# BaseSMD.net
KiCad netlist of a schematic drawn in EAGLE
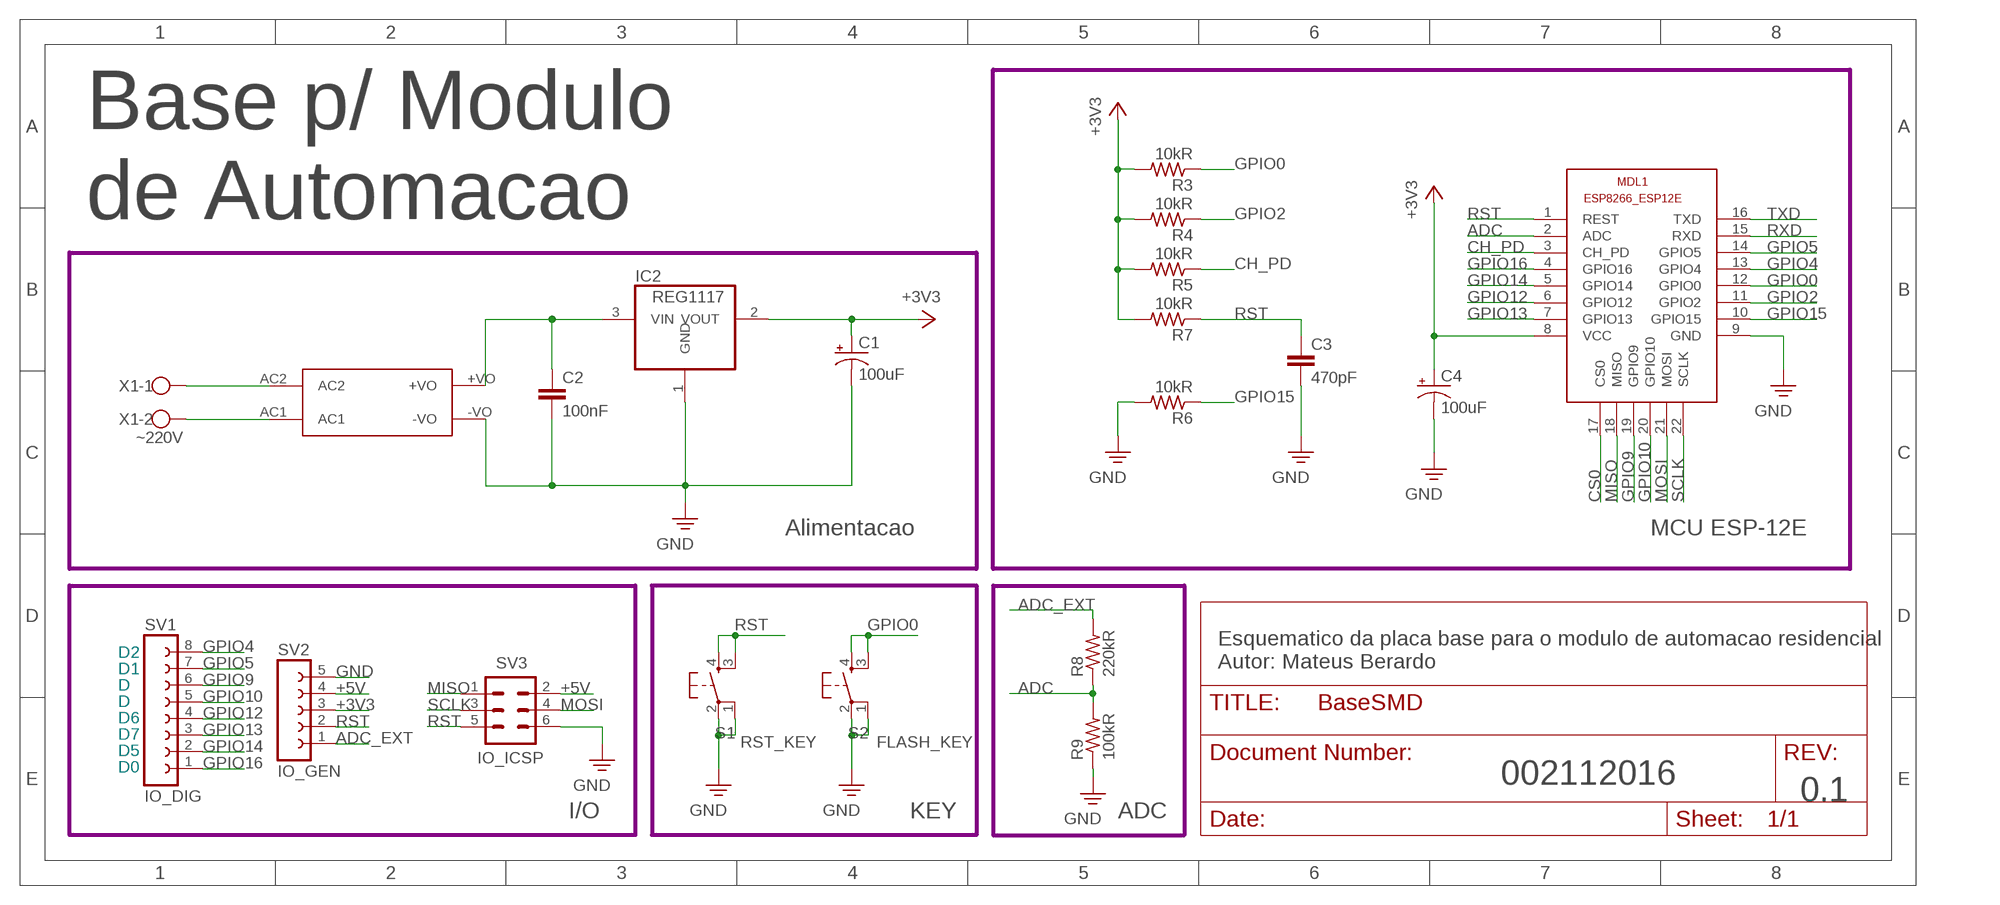
[diagram p0: schematic, sheet 1]

(export (version "E")
  (design (tool "Eeschema 10.0.6"))
  (components
    (comp (ref "C1")
      (value "100uF")
      (footprint "eagle-import:153CLV-0810")
      (libsource (lib "eagle-import") (part "CPOL-US153CLV-0810"))
    )
    (comp (ref "C2")
      (value "100nF")
      (footprint "eagle-import:C1206")
      (libsource (lib "eagle-import") (part "C-EUC1206"))
    )
    (comp (ref "C3")
      (value "470pF")
      (footprint "eagle-import:C1206")
      (libsource (lib "eagle-import") (part "C-EUC1206"))
    )
    (comp (ref "C4")
      (value "100uF")
      (footprint "eagle-import:153CLV-0810")
      (libsource (lib "eagle-import") (part "CPOL-US153CLV-0810"))
    )
    (comp (ref "IC2")
      (value "REG1117")
      (footprint "eagle-import:SOT223")
      (libsource (lib "eagle-import") (part "REG1117"))
    )
    (comp (ref "MDL1")
      (value "MCU ESP")
      (footprint "eagle-import:ESP8266-ESP12E")
      (libsource (lib "eagle-import") (part "ESP8266-12EESP8266-ESP12E"))
    )
    (comp (ref "R3")
      (value "10kR")
      (footprint "eagle-import:M1206")
      (libsource (lib "eagle-import") (part "R-US_M1206"))
    )
    (comp (ref "R4")
      (value "10kR")
      (footprint "eagle-import:M1206")
      (libsource (lib "eagle-import") (part "R-US_M1206"))
    )
    (comp (ref "R5")
      (value "10kR")
      (footprint "eagle-import:M1206")
      (libsource (lib "eagle-import") (part "R-US_M1206"))
    )
    (comp (ref "R6")
      (value "10kR")
      (footprint "eagle-import:M1206")
      (libsource (lib "eagle-import") (part "R-US_M1206"))
    )
    (comp (ref "R7")
      (value "10kR")
      (footprint "eagle-import:M1206")
      (libsource (lib "eagle-import") (part "R-US_M1206"))
    )
    (comp (ref "R8")
      (value "220kR")
      (footprint "eagle-import:R1206")
      (libsource (lib "eagle-import") (part "R-US_R1206"))
    )
    (comp (ref "R9")
      (value "100kR")
      (footprint "eagle-import:R1206")
      (libsource (lib "eagle-import") (part "R-US_R1206"))
    )
    (comp (ref "S1")
      (value "RST_KEY")
      (footprint "eagle-import:BT4X4")
      (libsource (lib "eagle-import") (part "10-XX4X4SMD"))
    )
    (comp (ref "S2")
      (value "FLASH_KEY")
      (footprint "eagle-import:BT4X4")
      (libsource (lib "eagle-import") (part "10-XX4X4SMD"))
    )
    (comp (ref "SV1")
      (value "IO_DIG")
      (footprint "eagle-import:FE08")
      (libsource (lib "eagle-import") (part "FE08-1"))
    )
    (comp (ref "SV2")
      (value "IO_GEN")
      (footprint "eagle-import:FE05-1")
      (libsource (lib "eagle-import") (part "FE05-1"))
    )
    (comp (ref "SV3")
      (value "IO_ICSP")
      (footprint "eagle-import:MA03-2")
      (libsource (lib "eagle-import") (part "MA03-2"))
    )
    (comp (ref "U$1")
      (value "HLK-PM01")
      (footprint "eagle-import:HLK-PM01")
      (libsource (lib "eagle-import") (part "HLK-PM01"))
    )
    (comp (ref "X1")
      (value "~220V")
      (footprint "eagle-import:W237-102")
      (fields (field (name "MPN") "237-102"))
      (libsource (lib "eagle-import") (part "W237-102"))
    )
  )
  (nets
    (net (code "1") (name "+3V3") (class "Default")
      (node (ref "C1") (pin "+") (pinfunction "+_+") (pintype "passive"))
      (node (ref "C4") (pin "+") (pinfunction "+_+") (pintype "passive"))
      (node (ref "IC2") (pin "2") (pinfunction "VOUT_2") (pintype "output"))
      (node (ref "MDL1") (pin "8") (pinfunction "VCC_8") (pintype "bidirectional"))
      (node (ref "R3") (pin "2") (pinfunction "2_2") (pintype "passive"))
      (node (ref "R4") (pin "2") (pinfunction "2_2") (pintype "passive"))
      (node (ref "R5") (pin "2") (pinfunction "2_2") (pintype "passive"))
      (node (ref "R7") (pin "2") (pinfunction "2_2") (pintype "passive"))
      (node (ref "SV2") (pin "3") (pinfunction "3_3") (pintype "passive"))
    )
    (net (code "2") (name "/+5V") (class "Default")
      (node (ref "C2") (pin "1") (pinfunction "1_1") (pintype "passive"))
      (node (ref "IC2") (pin "3") (pinfunction "VIN_3") (pintype "input"))
      (node (ref "SV2") (pin "4") (pinfunction "4_4") (pintype "passive"))
      (node (ref "SV3") (pin "2") (pinfunction "2_2") (pintype "passive"))
      (node (ref "U$1") (pin "+VO") (pinfunction "+VO_+VO") (pintype "bidirectional"))
    )
    (net (code "3") (name "/ADC") (class "Default")
      (node (ref "MDL1") (pin "2") (pinfunction "ADC_2") (pintype "bidirectional"))
      (node (ref "R8") (pin "1") (pinfunction "1_1") (pintype "passive"))
      (node (ref "R9") (pin "2") (pinfunction "2_2") (pintype "passive"))
    )
    (net (code "4") (name "/ADC_EXT") (class "Default")
      (node (ref "R8") (pin "2") (pinfunction "2_2") (pintype "passive"))
      (node (ref "SV2") (pin "1") (pinfunction "1_1") (pintype "passive"))
    )
    (net (code "5") (name "/CH_PD") (class "Default")
      (node (ref "MDL1") (pin "3") (pinfunction "CH_PD_3") (pintype "bidirectional"))
      (node (ref "R5") (pin "1") (pinfunction "1_1") (pintype "passive"))
    )
    (net (code "6") (name "/CS0") (class "Default")
      (node (ref "MDL1") (pin "17") (pinfunction "CS0_17") (pintype "bidirectional"))
    )
    (net (code "7") (name "/GPIO0") (class "Default")
      (node (ref "MDL1") (pin "12") (pinfunction "GPIO0_12") (pintype "bidirectional"))
      (node (ref "R3") (pin "1") (pinfunction "1_1") (pintype "passive"))
      (node (ref "S2") (pin "3") (pinfunction "S1_3") (pintype "passive"))
      (node (ref "S2") (pin "4") (pinfunction "S_4") (pintype "passive"))
    )
    (net (code "8") (name "/GPIO2") (class "Default")
      (node (ref "MDL1") (pin "11") (pinfunction "GPIO2_11") (pintype "bidirectional"))
      (node (ref "R4") (pin "1") (pinfunction "1_1") (pintype "passive"))
    )
    (net (code "9") (name "/GPIO4") (class "Default")
      (node (ref "MDL1") (pin "13") (pinfunction "GPIO4_13") (pintype "bidirectional"))
      (node (ref "SV1") (pin "8") (pinfunction "8_8") (pintype "passive"))
    )
    (net (code "10") (name "/GPIO5") (class "Default")
      (node (ref "MDL1") (pin "14") (pinfunction "GPIO5_14") (pintype "bidirectional"))
      (node (ref "SV1") (pin "7") (pinfunction "7_7") (pintype "passive"))
    )
    (net (code "11") (name "/GPIO9") (class "Default")
      (node (ref "MDL1") (pin "19") (pinfunction "GPIO9_19") (pintype "bidirectional"))
      (node (ref "SV1") (pin "6") (pinfunction "6_6") (pintype "passive"))
    )
    (net (code "12") (name "/GPIO10") (class "Default")
      (node (ref "MDL1") (pin "20") (pinfunction "GPIO10_20") (pintype "bidirectional"))
      (node (ref "SV1") (pin "5") (pinfunction "5_5") (pintype "passive"))
    )
    (net (code "13") (name "/GPIO12") (class "Default")
      (node (ref "MDL1") (pin "6") (pinfunction "GPIO12_6") (pintype "bidirectional"))
      (node (ref "SV1") (pin "4") (pinfunction "4_4") (pintype "passive"))
    )
    (net (code "14") (name "/GPIO13") (class "Default")
      (node (ref "MDL1") (pin "7") (pinfunction "GPIO13_7") (pintype "bidirectional"))
      (node (ref "SV1") (pin "3") (pinfunction "3_3") (pintype "passive"))
    )
    (net (code "15") (name "/GPIO14") (class "Default")
      (node (ref "MDL1") (pin "5") (pinfunction "GPIO14_5") (pintype "bidirectional"))
      (node (ref "SV1") (pin "2") (pinfunction "2_2") (pintype "passive"))
    )
    (net (code "16") (name "/GPIO15") (class "Default")
      (node (ref "MDL1") (pin "10") (pinfunction "GPIO15_10") (pintype "bidirectional"))
      (node (ref "R6") (pin "1") (pinfunction "1_1") (pintype "passive"))
    )
    (net (code "17") (name "/GPIO16") (class "Default")
      (node (ref "MDL1") (pin "4") (pinfunction "GPIO16_4") (pintype "bidirectional"))
      (node (ref "SV1") (pin "1") (pinfunction "1_1") (pintype "passive"))
    )
    (net (code "18") (name "/MISO") (class "Default")
      (node (ref "MDL1") (pin "18") (pinfunction "MISO_18") (pintype "bidirectional"))
      (node (ref "SV3") (pin "1") (pinfunction "1_1") (pintype "passive"))
    )
    (net (code "19") (name "/MOSI") (class "Default")
      (node (ref "MDL1") (pin "21") (pinfunction "MOSI_21") (pintype "bidirectional"))
      (node (ref "SV3") (pin "4") (pinfunction "4_4") (pintype "passive"))
    )
    (net (code "20") (name "/RST") (class "Default")
      (node (ref "C3") (pin "1") (pinfunction "1_1") (pintype "passive"))
      (node (ref "MDL1") (pin "1") (pinfunction "REST_1") (pintype "bidirectional"))
      (node (ref "R7") (pin "1") (pinfunction "1_1") (pintype "passive"))
      (node (ref "S1") (pin "3") (pinfunction "S1_3") (pintype "passive"))
      (node (ref "S1") (pin "4") (pinfunction "S_4") (pintype "passive"))
      (node (ref "SV2") (pin "2") (pinfunction "2_2") (pintype "passive"))
      (node (ref "SV3") (pin "5") (pinfunction "5_5") (pintype "passive"))
    )
    (net (code "21") (name "/RXD") (class "Default")
      (node (ref "MDL1") (pin "15") (pinfunction "RXD_15") (pintype "bidirectional"))
    )
    (net (code "22") (name "/SCLK") (class "Default")
      (node (ref "MDL1") (pin "22") (pinfunction "SCLK_22") (pintype "bidirectional"))
      (node (ref "SV3") (pin "3") (pinfunction "3_3") (pintype "passive"))
    )
    (net (code "23") (name "/TXD") (class "Default")
      (node (ref "MDL1") (pin "16") (pinfunction "TXD_16") (pintype "bidirectional"))
    )
    (net (code "24") (name "GND") (class "Default")
      (node (ref "C1") (pin "-") (pinfunction "-_-") (pintype "passive"))
      (node (ref "C2") (pin "2") (pinfunction "2_2") (pintype "passive"))
      (node (ref "C3") (pin "2") (pinfunction "2_2") (pintype "passive"))
      (node (ref "C4") (pin "-") (pinfunction "-_-") (pintype "passive"))
      (node (ref "IC2") (pin "1") (pinfunction "GND_1") (pintype "power_in"))
      (node (ref "MDL1") (pin "9") (pinfunction "GND_9") (pintype "bidirectional"))
      (node (ref "R6") (pin "2") (pinfunction "2_2") (pintype "passive"))
      (node (ref "R9") (pin "1") (pinfunction "1_1") (pintype "passive"))
      (node (ref "S1") (pin "1") (pinfunction "P1_1") (pintype "passive"))
      (node (ref "S1") (pin "2") (pinfunction "P_2") (pintype "passive"))
      (node (ref "S2") (pin "1") (pinfunction "P1_1") (pintype "passive"))
      (node (ref "S2") (pin "2") (pinfunction "P_2") (pintype "passive"))
      (node (ref "SV2") (pin "5") (pinfunction "5_5") (pintype "passive"))
      (node (ref "SV3") (pin "6") (pinfunction "6_6") (pintype "passive"))
      (node (ref "U$1") (pin "-VO") (pinfunction "-VO_-VO") (pintype "bidirectional"))
    )
    (net (code "25") (name "Net-(X1A-KL)") (class "Default")
      (node (ref "U$1") (pin "AC2") (pinfunction "AC2_AC2") (pintype "bidirectional"))
      (node (ref "X1") (pin "1") (pinfunction "KL_1") (pintype "passive"))
    )
    (net (code "26") (name "Net-(X1B-KL)") (class "Default")
      (node (ref "U$1") (pin "AC1") (pinfunction "AC1_AC1") (pintype "bidirectional"))
      (node (ref "X1") (pin "2") (pinfunction "KL_2") (pintype "passive"))
    )
  )
)
